# SparkFun_GPS_ZED-F9K.net
KiCad netlist of a schematic drawn in EAGLE
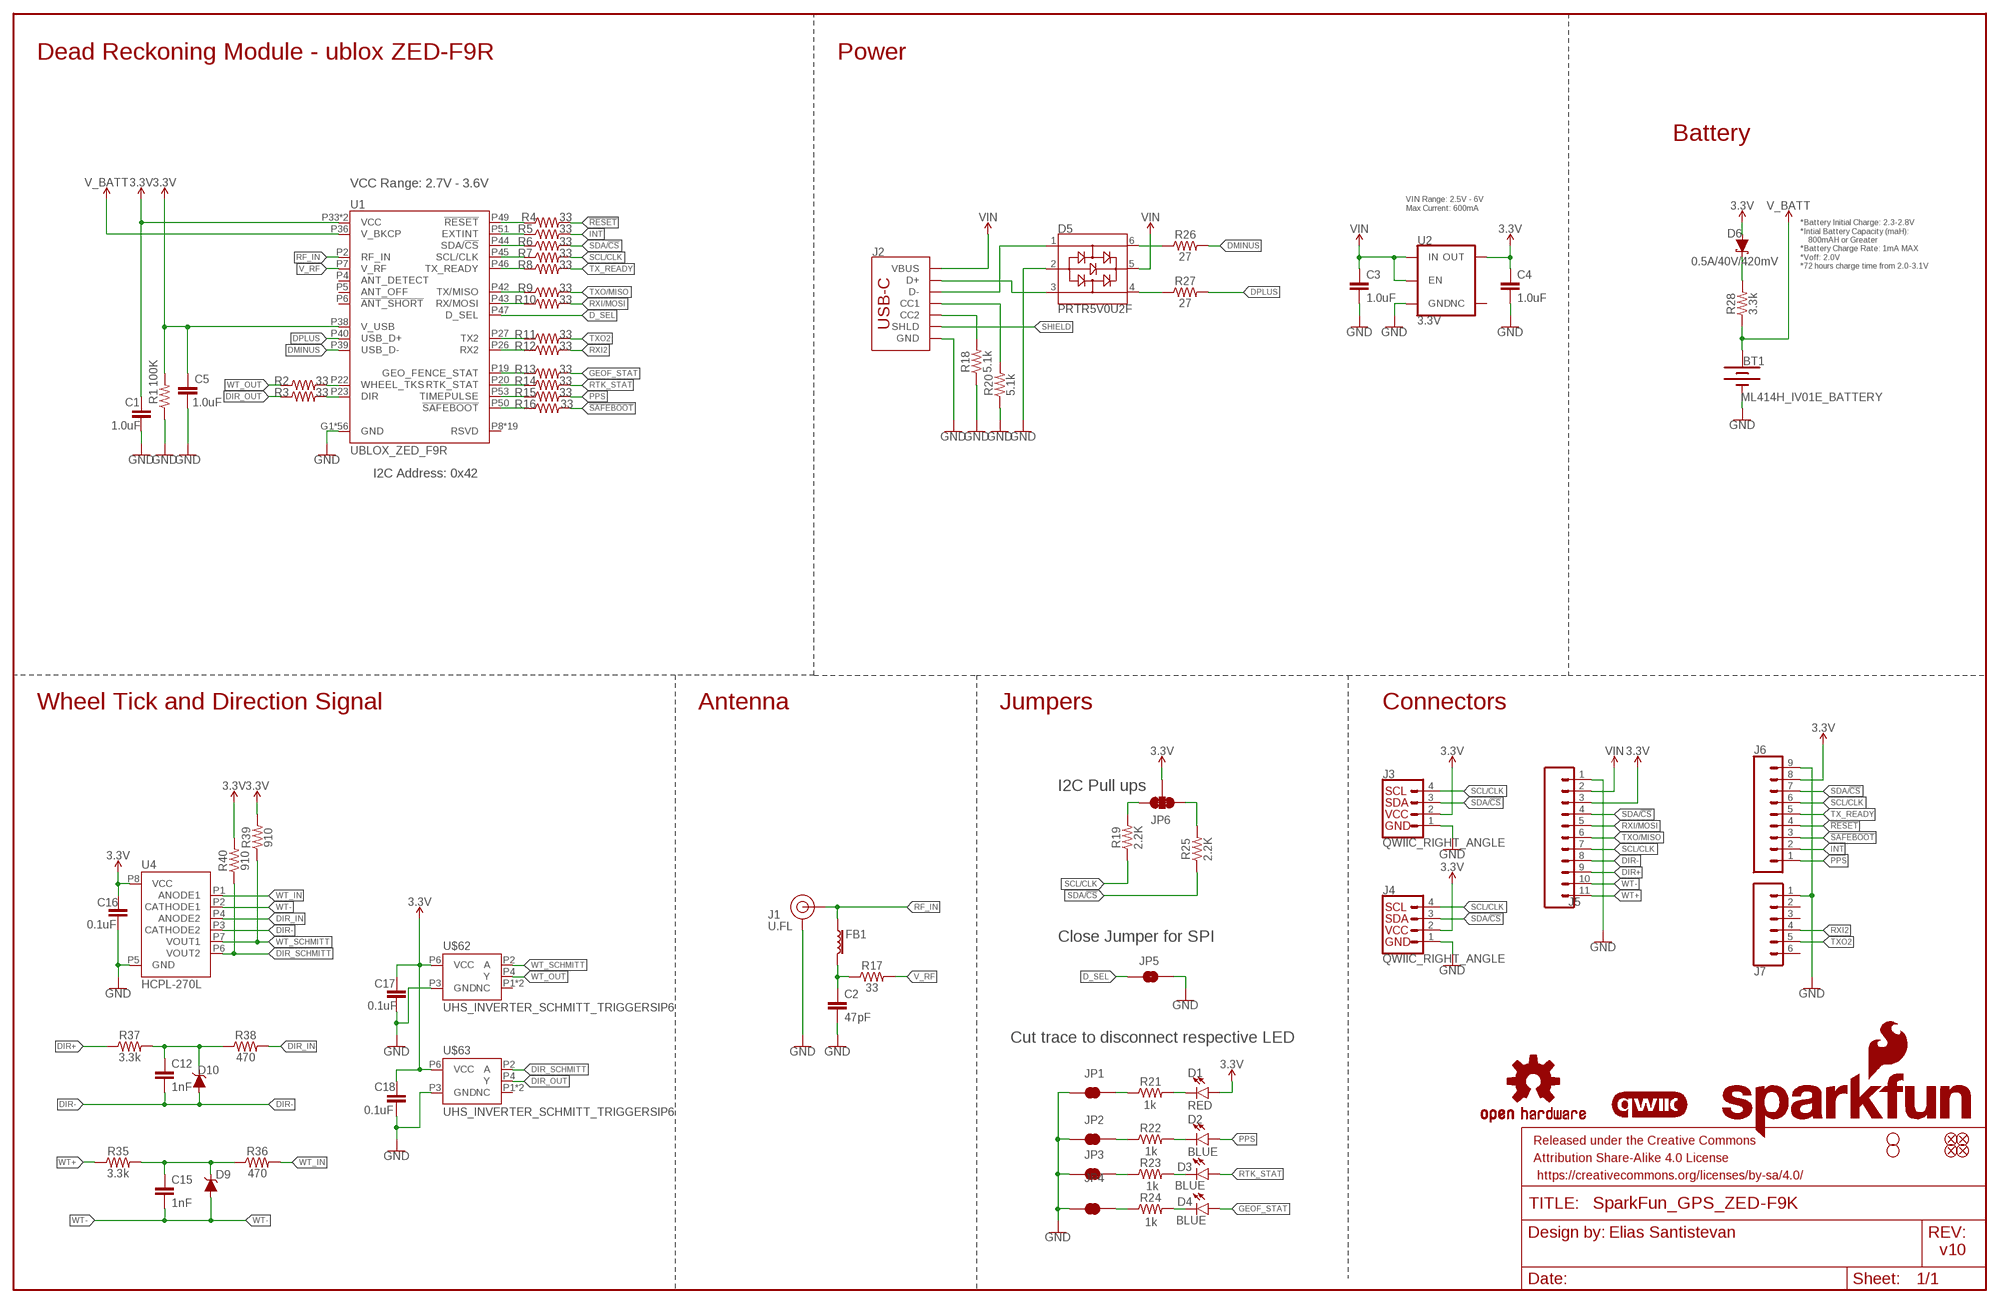
[diagram p0: schematic, sheet 1]

(export (version "E")
  (design (tool "Eeschema 10.0.6"))
  (components
    (comp (ref "$1_36_$_2020-02-13_17-32-45")
      (value "STAND-OFFTIGHT")
      (footprint "eagle-import:STAND-OFF-TIGHT")
      (libsource (lib "eagle-import") (part "STAND-OFFTIGHT"))
    )
    (comp (ref "BT1")
      (value "ML414H_IV01E_BATTERY")
      (footprint "eagle-import:ML414H_IV01E")
      (libsource (lib "eagle-import") (part "ML414H_IV01E_BATTERY"))
    )
    (comp (ref "C1")
      (value "1.0uF")
      (footprint "eagle-import:0603")
      (libsource (lib "eagle-import") (part "1.0UF-0603-16V-10%-X7R"))
    )
    (comp (ref "C2")
      (value "47pF")
      (footprint "eagle-import:0402")
      (libsource (lib "eagle-import") (part "47PF-0402-25V-5%-X7R"))
    )
    (comp (ref "C3")
      (value "1.0uF")
      (footprint "eagle-import:0603")
      (libsource (lib "eagle-import") (part "1.0UF-0603-16V-10%-X7R"))
    )
    (comp (ref "C4")
      (value "1.0uF")
      (footprint "eagle-import:0603")
      (libsource (lib "eagle-import") (part "1.0UF-0603-16V-10%-X7R"))
    )
    (comp (ref "C5")
      (value "1.0uF")
      (footprint "eagle-import:0603")
      (libsource (lib "eagle-import") (part "1.0UF-0603-16V-10%-X7R"))
    )
    (comp (ref "C12")
      (value "1nF")
      (footprint "eagle-import:0402")
      (libsource (lib "eagle-import") (part "1.0NF/1000PF-0402-25V-10%-X7R"))
    )
    (comp (ref "C15")
      (value "1nF")
      (footprint "eagle-import:0402")
      (libsource (lib "eagle-import") (part "1.0NF/1000PF-0402-25V-10%-X7R"))
    )
    (comp (ref "C16")
      (value "0.1uF")
      (footprint "eagle-import:0402")
      (libsource (lib "eagle-import") (part "0.1UF-0402-6.3V-10%-X7R"))
    )
    (comp (ref "C17")
      (value "0.1uF")
      (footprint "eagle-import:0402")
      (libsource (lib "eagle-import") (part "0.1UF-0402-6.3V-10%-X7R"))
    )
    (comp (ref "C18")
      (value "0.1uF")
      (footprint "eagle-import:0402")
      (libsource (lib "eagle-import") (part "0.1UF-0402-6.3V-10%-X7R"))
    )
    (comp (ref "D1")
      (value "RED")
      (footprint "eagle-import:LED-0603")
      (libsource (lib "eagle-import") (part "LED-RED0603"))
    )
    (comp (ref "D2")
      (value "BLUE")
      (footprint "eagle-import:LED-0603")
      (libsource (lib "eagle-import") (part "LED-BLUE0603"))
    )
    (comp (ref "D3")
      (value "BLUE")
      (footprint "eagle-import:LED-0603")
      (libsource (lib "eagle-import") (part "LED-BLUE0603"))
    )
    (comp (ref "D4")
      (value "BLUE")
      (footprint "eagle-import:LED-0603")
      (libsource (lib "eagle-import") (part "LED-BLUE0603"))
    )
    (comp (ref "D5")
      (value "PRTR5V0U2F")
      (footprint "eagle-import:SOT886")
      (libsource (lib "eagle-import") (part "PRTR5V0U2F"))
    )
    (comp (ref "D6")
      (value "0.5A/40V/420mV")
      (footprint "eagle-import:SOD-323")
      (libsource (lib "eagle-import") (part "DIODE-SCHOTTKY-PMEG4005EJ"))
    )
    (comp (ref "D9")
      (value "0.5A/40V/420mV")
      (footprint "eagle-import:SOT23_BZX")
      (libsource (lib "eagle-import") (part "BZX84_DIODE"))
    )
    (comp (ref "D10")
      (value "0.5A/40V/420mV")
      (footprint "eagle-import:SOT23_BZX")
      (libsource (lib "eagle-import") (part "BZX84_DIODE"))
    )
    (comp (ref "FB1")
      (value "120NH")
      (footprint "eagle-import:0402_MURATA")
      (libsource (lib "eagle-import") (part "FERRITE_BEAD_GNSS"))
    )
    (comp (ref "FD1")
      (value "FIDUCIALUFIDUCIAL")
      (footprint "eagle-import:FIDUCIAL-MICRO")
      (libsource (lib "eagle-import") (part "FIDUCIALUFIDUCIAL"))
    )
    (comp (ref "FD2")
      (value "FIDUCIALUFIDUCIAL")
      (footprint "eagle-import:FIDUCIAL-MICRO")
      (libsource (lib "eagle-import") (part "FIDUCIALUFIDUCIAL"))
    )
    (comp (ref "FD3")
      (value "FIDUCIALUFIDUCIAL")
      (footprint "eagle-import:FIDUCIAL-MICRO")
      (libsource (lib "eagle-import") (part "FIDUCIALUFIDUCIAL"))
    )
    (comp (ref "FD4")
      (value "FIDUCIALUFIDUCIAL")
      (footprint "eagle-import:FIDUCIAL-MICRO")
      (libsource (lib "eagle-import") (part "FIDUCIALUFIDUCIAL"))
    )
    (comp (ref "FRAME1")
      (value "FRAME-LEDGER")
      (footprint "eagle-import:CREATIVE_COMMONS")
      (libsource (lib "eagle-import") (part "FRAME-LEDGER"))
    )
    (comp (ref "H2")
      (value "STAND-OFFTIGHT")
      (footprint "eagle-import:STAND-OFF-TIGHT")
      (libsource (lib "eagle-import") (part "STAND-OFFTIGHT"))
    )
    (comp (ref "J1")
      (value "U.FL")
      (footprint "eagle-import:U.FL")
      (libsource (lib "eagle-import") (part "U.FL2PIN"))
    )
    (comp (ref "J2")
      (value "USB_C_2-LAYER_PADS")
      (footprint "eagle-import:USB-C-16P-2LAYER-PADS")
      (libsource (lib "eagle-import") (part "USB_C_2-LAYER_PADS"))
    )
    (comp (ref "J3")
      (value "QWIIC_RIGHT_ANGLE")
      (footprint "eagle-import:JST04_1MM_RA")
      (libsource (lib "eagle-import") (part "QWIIC_CONNECTORJS-1MM"))
    )
    (comp (ref "J4")
      (value "QWIIC_RIGHT_ANGLE")
      (footprint "eagle-import:JST04_1MM_RA")
      (libsource (lib "eagle-import") (part "QWIIC_CONNECTORJS-1MM"))
    )
    (comp (ref "J5")
      (value "CONN_111X11_NO_SILK")
      (footprint "eagle-import:1X11_NO_SILK")
      (libsource (lib "eagle-import") (part "CONN_111X11_NO_SILK"))
    )
    (comp (ref "J6")
      (value "CONN_09NO_SILK")
      (footprint "eagle-import:1X09_NO_SILK")
      (libsource (lib "eagle-import") (part "CONN_09NO_SILK"))
    )
    (comp (ref "J7")
      (value "CONN_06NO_SILK_NO_POP")
      (footprint "eagle-import:1X06_NO_SILK")
      (libsource (lib "eagle-import") (part "CONN_06NO_SILK_NO_POP"))
    )
    (comp (ref "JP1")
      (value "JUMPER-SMT_2_NC_TRACE_SILK")
      (footprint "eagle-import:SMT-JUMPER_2_NC_TRACE_SILK")
      (libsource (lib "eagle-import") (part "JUMPER-SMT_2_NC_TRACE_SILK"))
    )
    (comp (ref "JP2")
      (value "JUMPER-SMT_2_NC_TRACE_SILK")
      (footprint "eagle-import:SMT-JUMPER_2_NC_TRACE_SILK")
      (libsource (lib "eagle-import") (part "JUMPER-SMT_2_NC_TRACE_SILK"))
    )
    (comp (ref "JP3")
      (value "JUMPER-SMT_2_NC_TRACE_SILK")
      (footprint "eagle-import:SMT-JUMPER_2_NC_TRACE_SILK")
      (libsource (lib "eagle-import") (part "JUMPER-SMT_2_NC_TRACE_SILK"))
    )
    (comp (ref "JP4")
      (value "JUMPER-SMT_2_NC_TRACE_SILK")
      (footprint "eagle-import:SMT-JUMPER_2_NC_TRACE_SILK")
      (libsource (lib "eagle-import") (part "JUMPER-SMT_2_NC_TRACE_SILK"))
    )
    (comp (ref "JP5")
      (value "JUMPER-SMT_2_NO_SILK")
      (footprint "eagle-import:SMT-JUMPER_2_NO_SILK")
      (libsource (lib "eagle-import") (part "JUMPER-SMT_2_NO_SILK"))
    )
    (comp (ref "JP6")
      (value "JUMPER-SMT_3_2-NC_TRACE_SILK")
      (footprint "eagle-import:SMT-JUMPER_3_2-NC_TRACE_SILK")
      (libsource (lib "eagle-import") (part "JUMPER-SMT_3_2-NC_TRACE_SILK"))
    )
    (comp (ref "LOGO1")
      (value "OSHW-LOGOM")
      (footprint "eagle-import:OSHW-LOGO-M")
      (libsource (lib "eagle-import") (part "OSHW-LOGOM"))
    )
    (comp (ref "LOGO2")
      (value "QWIIC_LOGO_4MM")
      (footprint "eagle-import:QWIIC_4MM")
      (libsource (lib "eagle-import") (part "QWIIC_LOGO_4MM"))
    )
    (comp (ref "LOGO3")
      (value "SFE_LOGO_NAME_FLAME.2_INCH")
      (footprint "eagle-import:SFE_LOGO_NAME_FLAME_.2")
      (libsource (lib "eagle-import") (part "SFE_LOGO_NAME_FLAME.2_INCH"))
    )
    (comp (ref "R1")
      (value "100K")
      (footprint "eagle-import:0402")
      (libsource (lib "eagle-import") (part "100KOHM-0402-1/16W-1%"))
    )
    (comp (ref "R2")
      (value "33")
      (footprint "eagle-import:0402")
      (libsource (lib "eagle-import") (part "33OHM-0402-1/10W-1%"))
    )
    (comp (ref "R3")
      (value "33")
      (footprint "eagle-import:0402")
      (libsource (lib "eagle-import") (part "33OHM-0402-1/10W-1%"))
    )
    (comp (ref "R4")
      (value "33")
      (footprint "eagle-import:0402")
      (libsource (lib "eagle-import") (part "33OHM-0402-1/10W-1%"))
    )
    (comp (ref "R5")
      (value "33")
      (footprint "eagle-import:0402")
      (libsource (lib "eagle-import") (part "33OHM-0402-1/10W-1%"))
    )
    (comp (ref "R6")
      (value "33")
      (footprint "eagle-import:0402")
      (libsource (lib "eagle-import") (part "33OHM-0402-1/10W-1%"))
    )
    (comp (ref "R7")
      (value "33")
      (footprint "eagle-import:0402")
      (libsource (lib "eagle-import") (part "33OHM-0402-1/10W-1%"))
    )
    (comp (ref "R8")
      (value "33")
      (footprint "eagle-import:0402")
      (libsource (lib "eagle-import") (part "33OHM-0402-1/10W-1%"))
    )
    (comp (ref "R9")
      (value "33")
      (footprint "eagle-import:0402")
      (libsource (lib "eagle-import") (part "33OHM-0402-1/10W-1%"))
    )
    (comp (ref "R10")
      (value "33")
      (footprint "eagle-import:0402")
      (libsource (lib "eagle-import") (part "33OHM-0402-1/10W-1%"))
    )
    (comp (ref "R11")
      (value "33")
      (footprint "eagle-import:0402")
      (libsource (lib "eagle-import") (part "33OHM-0402-1/10W-1%"))
    )
    (comp (ref "R12")
      (value "33")
      (footprint "eagle-import:0402")
      (libsource (lib "eagle-import") (part "33OHM-0402-1/10W-1%"))
    )
    (comp (ref "R13")
      (value "33")
      (footprint "eagle-import:0402")
      (libsource (lib "eagle-import") (part "33OHM-0402-1/10W-1%"))
    )
    (comp (ref "R14")
      (value "33")
      (footprint "eagle-import:0402")
      (libsource (lib "eagle-import") (part "33OHM-0402-1/10W-1%"))
    )
    (comp (ref "R15")
      (value "33")
      (footprint "eagle-import:0402")
      (libsource (lib "eagle-import") (part "33OHM-0402-1/10W-1%"))
    )
    (comp (ref "R16")
      (value "33")
      (footprint "eagle-import:0402")
      (libsource (lib "eagle-import") (part "33OHM-0402-1/10W-1%"))
    )
    (comp (ref "R17")
      (value "33")
      (footprint "eagle-import:0603")
      (libsource (lib "eagle-import") (part "33OHM-0603-1/10W-1%"))
    )
    (comp (ref "R18")
      (value "5.1k")
      (footprint "eagle-import:0402")
      (libsource (lib "eagle-import") (part "5.1KOHM-0402-1/16W-1%"))
    )
    (comp (ref "R19")
      (value "2.2K")
      (footprint "eagle-import:0402")
      (libsource (lib "eagle-import") (part "2.2KOHM-0402-1/16W-1%"))
    )
    (comp (ref "R20")
      (value "5.1k")
      (footprint "eagle-import:0402")
      (libsource (lib "eagle-import") (part "5.1KOHM-0402-1/16W-1%"))
    )
    (comp (ref "R21")
      (value "1KOHM-0402-1/16W-1%")
      (footprint "eagle-import:0402")
      (libsource (lib "eagle-import") (part "1KOHM-0402-1/16W-1%"))
    )
    (comp (ref "R22")
      (value "1KOHM-0402-1/16W-1%")
      (footprint "eagle-import:0402")
      (libsource (lib "eagle-import") (part "1KOHM-0402-1/16W-1%"))
    )
    (comp (ref "R23")
      (value "1KOHM-0402-1/16W-1%")
      (footprint "eagle-import:0402")
      (libsource (lib "eagle-import") (part "1KOHM-0402-1/16W-1%"))
    )
    (comp (ref "R24")
      (value "1KOHM-0402-1/16W-1%")
      (footprint "eagle-import:0402")
      (libsource (lib "eagle-import") (part "1KOHM-0402-1/16W-1%"))
    )
    (comp (ref "R25")
      (value "2.2K")
      (footprint "eagle-import:0402")
      (libsource (lib "eagle-import") (part "2.2KOHM-0402-1/16W-1%"))
    )
    (comp (ref "R26")
      (value "27")
      (footprint "eagle-import:0603")
      (libsource (lib "eagle-import") (part "27OHM-0603-1/10W-1%"))
    )
    (comp (ref "R27")
      (value "27")
      (footprint "eagle-import:0603")
      (libsource (lib "eagle-import") (part "27OHM-0603-1/10W-1%"))
    )
    (comp (ref "R28")
      (value "3.3k")
      (footprint "eagle-import:0603")
      (libsource (lib "eagle-import") (part "3.3KOHM-0603-1/10W-1%"))
    )
    (comp (ref "R35")
      (value "3.3k")
      (footprint "eagle-import:0603")
      (libsource (lib "eagle-import") (part "3.3KOHM-0603-1/10W-1%"))
    )
    (comp (ref "R36")
      (value "470")
      (footprint "eagle-import:0603")
      (libsource (lib "eagle-import") (part "470OHM-0603-1/10W-1%"))
    )
    (comp (ref "R37")
      (value "3.3k")
      (footprint "eagle-import:0603")
      (libsource (lib "eagle-import") (part "3.3KOHM-0603-1/10W-1%"))
    )
    (comp (ref "R38")
      (value "470")
      (footprint "eagle-import:0603")
      (libsource (lib "eagle-import") (part "470OHM-0603-1/10W-1%"))
    )
    (comp (ref "R39")
      (value "910")
      (footprint "eagle-import:0603")
      (libsource (lib "eagle-import") (part "910OHM-0603-1/10W-5%"))
    )
    (comp (ref "R40")
      (value "910")
      (footprint "eagle-import:0603")
      (libsource (lib "eagle-import") (part "910OHM-0603-1/10W-5%"))
    )
    (comp (ref "U$62")
      (value "UHS_INVERTER_SCHMITT_TRIGGERSIP6")
      (footprint "eagle-import:SIP6")
      (libsource (lib "eagle-import") (part "UHS_INVERTER_SCHMITT_TRIGGERSIP6"))
    )
    (comp (ref "U$63")
      (value "UHS_INVERTER_SCHMITT_TRIGGERSIP6")
      (footprint "eagle-import:SIP6")
      (libsource (lib "eagle-import") (part "UHS_INVERTER_SCHMITT_TRIGGERSIP6"))
    )
    (comp (ref "U1")
      (value "UBLOX_ZED_F9R")
      (footprint "eagle-import:UBLOX_ZED_F9R")
      (libsource (lib "eagle-import") (part "UBLOX_ZED_F9R"))
    )
    (comp (ref "U2")
      (value "3.3V")
      (footprint "eagle-import:SOT23-5")
      (libsource (lib "eagle-import") (part "V_REG_AP2112K-3.3V"))
    )
    (comp (ref "U4")
      (value "HCPL-270L")
      (footprint "eagle-import:SOP_8-PIN")
      (libsource (lib "eagle-import") (part "HCPL-270L"))
    )
  )
  (nets
    (net (code "1") (name "/SDA{slash}~{CS}") (class "Default")
      (node (ref "J3") (pin "3") (pinfunction "3_3") (pintype "passive"))
      (node (ref "J4") (pin "3") (pinfunction "3_3") (pintype "passive"))
      (node (ref "J5") (pin "4") (pinfunction "4_4") (pintype "passive"))
      (node (ref "J6") (pin "7") (pinfunction "7_7") (pintype "passive"))
      (node (ref "R25") (pin "1") (pinfunction "1_1") (pintype "passive"))
      (node (ref "R6") (pin "2") (pinfunction "2_2") (pintype "passive"))
    )
    (net (code "2") (name "/~{RESET}") (class "Default")
      (node (ref "J6") (pin "4") (pinfunction "4_4") (pintype "passive"))
      (node (ref "R4") (pin "2") (pinfunction "2_2") (pintype "passive"))
    )
    (net (code "3") (name "/~{SAFEBOOT}") (class "Default")
      (node (ref "J6") (pin "3") (pinfunction "3_3") (pintype "passive"))
      (node (ref "R16") (pin "2") (pinfunction "2_2") (pintype "passive"))
    )
    (net (code "4") (name "3.3V") (class "Default")
      (node (ref "C1") (pin "1") (pinfunction "1_1") (pintype "passive"))
      (node (ref "C16") (pin "1") (pinfunction "1_1") (pintype "passive"))
      (node (ref "C17") (pin "1") (pinfunction "1_1") (pintype "passive"))
      (node (ref "C18") (pin "1") (pinfunction "1_1") (pintype "passive"))
      (node (ref "C4") (pin "1") (pinfunction "1_1") (pintype "passive"))
      (node (ref "C5") (pin "1") (pinfunction "1_1") (pintype "passive"))
      (node (ref "D1") (pin "A") (pinfunction "A_A") (pintype "passive"))
      (node (ref "D6") (pin "A") (pinfunction "A_A") (pintype "passive"))
      (node (ref "J3") (pin "2") (pinfunction "2_2") (pintype "power_in"))
      (node (ref "J4") (pin "2") (pinfunction "2_2") (pintype "power_in"))
      (node (ref "J5") (pin "3") (pinfunction "3_3") (pintype "passive"))
      (node (ref "J6") (pin "8") (pinfunction "8_8") (pintype "passive"))
      (node (ref "JP6") (pin "2") (pinfunction "2_2") (pintype "passive"))
      (node (ref "R1") (pin "2") (pinfunction "2_2") (pintype "passive"))
      (node (ref "R39") (pin "2") (pinfunction "2_2") (pintype "passive"))
      (node (ref "R40") (pin "2") (pinfunction "2_2") (pintype "passive"))
      (node (ref "U$62") (pin "P6") (pinfunction "VCC_P6") (pintype "power_in"))
      (node (ref "U$63") (pin "P6") (pinfunction "VCC_P6") (pintype "power_in"))
      (node (ref "U1") (pin "P33") (pinfunction "VCC_P33") (pintype "power_in"))
      (node (ref "U1") (pin "P34") (pinfunction "VCC_P34") (pintype "power_in"))
      (node (ref "U1") (pin "P38") (pinfunction "V_USB_P38") (pintype "power_in"))
      (node (ref "U2") (pin "5") (pinfunction "OUT_5") (pintype "passive"))
      (node (ref "U4") (pin "P8") (pinfunction "VCC_P8") (pintype "power_in"))
    )
    (net (code "5") (name "DIR+") (class "Default")
      (node (ref "J5") (pin "9") (pinfunction "9_9") (pintype "passive"))
      (node (ref "R37") (pin "1") (pinfunction "1_1") (pintype "passive"))
    )
    (net (code "6") (name "DIR-") (class "Default")
      (node (ref "C12") (pin "2") (pinfunction "2_2") (pintype "passive"))
      (node (ref "D10") (pin "P1") (pinfunction "A_P1") (pintype "passive"))
      (node (ref "J5") (pin "8") (pinfunction "8_8") (pintype "passive"))
      (node (ref "U4") (pin "P3") (pinfunction "CATHODE2_P3") (pintype "input"))
    )
    (net (code "7") (name "DIR_IN") (class "Default")
      (node (ref "R38") (pin "2") (pinfunction "2_2") (pintype "passive"))
      (node (ref "U4") (pin "P4") (pinfunction "ANODE2_P4") (pintype "input"))
    )
    (net (code "8") (name "DIR_OUT") (class "Default")
      (node (ref "R3") (pin "1") (pinfunction "1_1") (pintype "passive"))
      (node (ref "U$63") (pin "P4") (pinfunction "Y_P4") (pintype "bidirectional"))
    )
    (net (code "9") (name "DIR_SCHMITT") (class "Default")
      (node (ref "R40") (pin "1") (pinfunction "1_1") (pintype "passive"))
      (node (ref "U$63") (pin "P2") (pinfunction "A_P2") (pintype "bidirectional"))
      (node (ref "U4") (pin "P6") (pinfunction "VOUT2_P6") (pintype "output"))
    )
    (net (code "10") (name "DMINUS") (class "Default")
      (node (ref "R26") (pin "2") (pinfunction "2_2") (pintype "passive"))
      (node (ref "U1") (pin "P39") (pinfunction "USB_D-_P39") (pintype "bidirectional"))
    )
    (net (code "11") (name "DPLUS") (class "Default")
      (node (ref "R27") (pin "2") (pinfunction "2_2") (pintype "passive"))
      (node (ref "U1") (pin "P40") (pinfunction "USB_D+_P40") (pintype "bidirectional"))
    )
    (net (code "12") (name "D_SEL") (class "Default")
      (node (ref "JP5") (pin "1") (pinfunction "1_1") (pintype "passive"))
      (node (ref "U1") (pin "P47") (pinfunction "D_SEL_P47") (pintype "bidirectional"))
    )
    (net (code "13") (name "GEOF_STAT") (class "Default")
      (node (ref "D4") (pin "A") (pinfunction "A_A") (pintype "passive"))
      (node (ref "R13") (pin "2") (pinfunction "2_2") (pintype "passive"))
    )
    (net (code "14") (name "GND") (class "Default")
      (node (ref "BT1") (pin "-") (pinfunction "-_-") (pintype "power_in"))
      (node (ref "C1") (pin "2") (pinfunction "2_2") (pintype "passive"))
      (node (ref "C16") (pin "2") (pinfunction "2_2") (pintype "passive"))
      (node (ref "C17") (pin "2") (pinfunction "2_2") (pintype "passive"))
      (node (ref "C18") (pin "2") (pinfunction "2_2") (pintype "passive"))
      (node (ref "C2") (pin "2") (pinfunction "2_2") (pintype "passive"))
      (node (ref "C3") (pin "2") (pinfunction "2_2") (pintype "passive"))
      (node (ref "C4") (pin "2") (pinfunction "2_2") (pintype "passive"))
      (node (ref "C5") (pin "2") (pinfunction "2_2") (pintype "passive"))
      (node (ref "D5") (pin "2") (pinfunction "2_2") (pintype "bidirectional"))
      (node (ref "J1") (pin "1") (pinfunction "GND_1") (pintype "bidirectional"))
      (node (ref "J1") (pin "2") (pinfunction "GND_2") (pintype "bidirectional"))
      (node (ref "J2") (pin "GND") (pinfunction "GND_GND") (pintype "bidirectional"))
      (node (ref "J2") (pin "GND2") (pinfunction "GND_GND2") (pintype "bidirectional"))
      (node (ref "J3") (pin "1") (pinfunction "1_1") (pintype "power_in"))
      (node (ref "J4") (pin "1") (pinfunction "1_1") (pintype "power_in"))
      (node (ref "J5") (pin "1") (pinfunction "1_1") (pintype "passive"))
      (node (ref "J6") (pin "9") (pinfunction "9_9") (pintype "passive"))
      (node (ref "J7") (pin "1") (pinfunction "1_1") (pintype "passive"))
      (node (ref "JP1") (pin "1") (pinfunction "1_1") (pintype "passive"))
      (node (ref "JP2") (pin "1") (pinfunction "1_1") (pintype "passive"))
      (node (ref "JP3") (pin "1") (pinfunction "1_1") (pintype "passive"))
      (node (ref "JP4") (pin "1") (pinfunction "1_1") (pintype "passive"))
      (node (ref "JP5") (pin "2") (pinfunction "2_2") (pintype "passive"))
      (node (ref "R1") (pin "1") (pinfunction "1_1") (pintype "passive"))
      (node (ref "R18") (pin "1") (pinfunction "1_1") (pintype "passive"))
      (node (ref "R20") (pin "1") (pinfunction "1_1") (pintype "passive"))
      (node (ref "U$62") (pin "P3") (pinfunction "GND_P3") (pintype "power_in"))
      (node (ref "U$63") (pin "P3") (pinfunction "GND_P3") (pintype "power_in"))
      (node (ref "U1") (pin "G1") (pinfunction "GND_G1") (pintype "power_in"))
      (node (ref "U1") (pin "G10") (pinfunction "GND_G10") (pintype "power_in"))
      (node (ref "U1") (pin "G11") (pinfunction "GND_G11") (pintype "power_in"))
      (node (ref "U1") (pin "G12") (pinfunction "GND_G12") (pintype "power_in"))
      (node (ref "U1") (pin "G13") (pinfunction "GND_G13") (pintype "power_in"))
      (node (ref "U1") (pin "G14") (pinfunction "GND_G14") (pintype "power_in"))
      (node (ref "U1") (pin "G15") (pinfunction "GND_G15") (pintype "power_in"))
      (node (ref "U1") (pin "G16") (pinfunction "GND_G16") (pintype "power_in"))
      (node (ref "U1") (pin "G17") (pinfunction "GND_G17") (pintype "power_in"))
      (node (ref "U1") (pin "G18") (pinfunction "GND_G18") (pintype "power_in"))
      (node (ref "U1") (pin "G19") (pinfunction "GND_G19") (pintype "power_in"))
      (node (ref "U1") (pin "G2") (pinfunction "GND_G2") (pintype "power_in"))
      (node (ref "U1") (pin "G20") (pinfunction "GND_G20") (pintype "power_in"))
      (node (ref "U1") (pin "G21") (pinfunction "GND_G21") (pintype "power_in"))
      (node (ref "U1") (pin "G22") (pinfunction "GND_G22") (pintype "power_in"))
      (node (ref "U1") (pin "G23") (pinfunction "GND_G23") (pintype "power_in"))
      (node (ref "U1") (pin "G24") (pinfunction "GND_G24") (pintype "power_in"))
      (node (ref "U1") (pin "G25") (pinfunction "GND_G25") (pintype "power_in"))
      (node (ref "U1") (pin "G26") (pinfunction "GND_G26") (pintype "power_in"))
      (node (ref "U1") (pin "G27") (pinfunction "GND_G27") (pintype "power_in"))
      (node (ref "U1") (pin "G28") (pinfunction "GND_G28") (pintype "power_in"))
      (node (ref "U1") (pin "G29") (pinfunction "GND_G29") (pintype "power_in"))
      (node (ref "U1") (pin "G3") (pinfunction "GND_G3") (pintype "power_in"))
      (node (ref "U1") (pin "G30") (pinfunction "GND_G30") (pintype "power_in"))
      (node (ref "U1") (pin "G31") (pinfunction "GND_G31") (pintype "power_in"))
      (node (ref "U1") (pin "G32") (pinfunction "GND_G32") (pintype "power_in"))
      (node (ref "U1") (pin "G33") (pinfunction "GND_G33") (pintype "power_in"))
      (node (ref "U1") (pin "G34") (pinfunction "GND_G34") (pintype "power_in"))
      (node (ref "U1") (pin "G35") (pinfunction "GND_G35") (pintype "power_in"))
      (node (ref "U1") (pin "G36") (pinfunction "GND_G36") (pintype "power_in"))
      (node (ref "U1") (pin "G37") (pinfunction "GND_G37") (pintype "power_in"))
      (node (ref "U1") (pin "G38") (pinfunction "GND_G38") (pintype "power_in"))
      (node (ref "U1") (pin "G39") (pinfunction "GND_G39") (pintype "power_in"))
      (node (ref "U1") (pin "G4") (pinfunction "GND_G4") (pintype "power_in"))
      (node (ref "U1") (pin "G40") (pinfunction "GND_G40") (pintype "power_in"))
      (node (ref "U1") (pin "G41") (pinfunction "GND_G41") (pintype "power_in"))
      (node (ref "U1") (pin "G42") (pinfunction "GND_G42") (pintype "power_in"))
      (node (ref "U1") (pin "G43") (pinfunction "GND_G43") (pintype "power_in"))
      (node (ref "U1") (pin "G44") (pinfunction "GND_G44") (pintype "power_in"))
      (node (ref "U1") (pin "G45") (pinfunction "GND_G45") (pintype "power_in"))
      (node (ref "U1") (pin "G46") (pinfunction "GND_G46") (pintype "power_in"))
      (node (ref "U1") (pin "G47") (pinfunction "GND_G47") (pintype "power_in"))
      (node (ref "U1") (pin "G48") (pinfunction "GND_G48") (pintype "power_in"))
      (node (ref "U1") (pin "G5") (pinfunction "GND_G5") (pintype "power_in"))
      (node (ref "U1") (pin "G6") (pinfunction "GND_G6") (pintype "power_in"))
      (node (ref "U1") (pin "G7") (pinfunction "GND_G7") (pintype "power_in"))
      (node (ref "U1") (pin "G8") (pinfunction "GND_G8") (pintype "power_in"))
      (node (ref "U1") (pin "G9") (pinfunction "GND_G9") (pintype "power_in"))
      (node (ref "U1") (pin "P1") (pinfunction "GND_P1") (pintype "power_in"))
      (node (ref "U1") (pin "P12") (pinfunction "GND_P12") (pintype "power_in"))
      (node (ref "U1") (pin "P14") (pinfunction "GND_P14") (pintype "power_in"))
      (node (ref "U1") (pin "P3") (pinfunction "GND_P3") (pintype "power_in"))
      (node (ref "U1") (pin "P32") (pinfunction "GND_P32") (pintype "power_in"))
      (node (ref "U1") (pin "P37") (pinfunction "GND_P37") (pintype "power_in"))
      (node (ref "U1") (pin "P41") (pinfunction "GND_P41") (pintype "power_in"))
      (node (ref "U1") (pin "P48") (pinfunction "GND_P48") (pintype "power_in"))
      (node (ref "U2") (pin "2") (pinfunction "GND_2") (pintype "input"))
      (node (ref "U4") (pin "P5") (pinfunction "GND_P5") (pintype "power_in"))
    )
    (net (code "15") (name "INT") (class "Default")
      (node (ref "J6") (pin "2") (pinfunction "2_2") (pintype "passive"))
      (node (ref "R5") (pin "2") (pinfunction "2_2") (pintype "passive"))
    )
    (net (code "16") (name "Net-(D1-PadC)") (class "Default")
      (node (ref "D1") (pin "C") (pinfunction "C_C") (pintype "passive"))
      (node (ref "R21") (pin "2") (pinfunction "2_2") (pintype "passive"))
    )
    (net (code "17") (name "Net-(D2-PadC)") (class "Default")
      (node (ref "D2") (pin "C") (pinfunction "C_C") (pintype "passive"))
      (node (ref "R22") (pin "2") (pinfunction "2_2") (pintype "passive"))
    )
    (net (code "18") (name "Net-(D3-PadC)") (class "Default")
      (node (ref "D3") (pin "C") (pinfunction "C_C") (pintype "passive"))
      (node (ref "R23") (pin "2") (pinfunction "2_2") (pintype "passive"))
    )
    (net (code "19") (name "Net-(D4-PadC)") (class "Default")
      (node (ref "D4") (pin "C") (pinfunction "C_C") (pintype "passive"))
      (node (ref "R24") (pin "2") (pinfunction "2_2") (pintype "passive"))
    )
    (net (code "20") (name "Net-(D5-Pad1)") (class "Default")
      (node (ref "D5") (pin "1") (pinfunction "1_1") (pintype "bidirectional"))
      (node (ref "J2") (pin "A7") (pinfunction "D-_A7") (pintype "bidirectional"))
      (node (ref "J2") (pin "B7") (pinfunction "D-_B7") (pintype "bidirectional"))
    )
    (net (code "21") (name "Net-(D5-Pad3)") (class "Default")
      (node (ref "D5") (pin "3") (pinfunction "3_3") (pintype "bidirectional"))
      (node (ref "J2") (pin "A6") (pinfunction "D+_A6") (pintype "bidirectional"))
      (node (ref "J2") (pin "B6") (pinfunction "D+_B6") (pintype "bidirectional"))
    )
    (net (code "22") (name "Net-(D5-Pad4)") (class "Default")
      (node (ref "D5") (pin "4") (pinfunction "4_4") (pintype "bidirectional"))
      (node (ref "R27") (pin "1") (pinfunction "1_1") (pintype "passive"))
    )
    (net (code "23") (name "Net-(D5-Pad6)") (class "Default")
      (node (ref "D5") (pin "6") (pinfunction "6_6") (pintype "bidirectional"))
      (node (ref "R26") (pin "1") (pinfunction "1_1") (pintype "passive"))
    )
    (net (code "24") (name "Net-(D6-PadC)") (class "Default")
      (node (ref "D6") (pin "C") (pinfunction "C_C") (pintype "passive"))
      (node (ref "R28") (pin "2") (pinfunction "2_2") (pintype "passive"))
    )
    (net (code "25") (name "Net-(D9-C)") (class "Default")
      (node (ref "C15") (pin "1") (pinfunction "1_1") (pintype "passive"))
      (node (ref "D9") (pin "P3") (pinfunction "C_P3") (pintype "passive"))
      (node (ref "R35") (pin "2") (pinfunction "2_2") (pintype "passive"))
      (node (ref "R36") (pin "1") (pinfunction "1_1") (pintype "passive"))
    )
    (net (code "26") (name "Net-(D10-C)") (class "Default")
      (node (ref "C12") (pin "1") (pinfunction "1_1") (pintype "passive"))
      (node (ref "D10") (pin "P3") (pinfunction "C_P3") (pintype "passive"))
      (node (ref "R37") (pin "2") (pinfunction "2_2") (pintype "passive"))
      (node (ref "R38") (pin "1") (pinfunction "1_1") (pintype "passive"))
    )
    (net (code "27") (name "Net-(FB1-2)") (class "Default")
      (node (ref "C2") (pin "1") (pinfunction "1_1") (pintype "passive"))
      (node (ref "FB1") (pin "P2") (pinfunction "2_P2") (pintype "passive"))
      (node (ref "R17") (pin "1") (pinfunction "1_1") (pintype "passive"))
    )
    (net (code "28") (name "Net-(J2-CC1)") (class "Default")
      (node (ref "J2") (pin "A5") (pinfunction "CC1_A5") (pintype "bidirectional"))
      (node (ref "R20") (pin "2") (pinfunction "2_2") (pintype "passive"))
    )
    (net (code "29") (name "Net-(J2-CC2)") (class "Default")
      (node (ref "J2") (pin "B5") (pinfunction "CC2_B5") (pintype "bidirectional"))
      (node (ref "R18") (pin "2") (pinfunction "2_2") (pintype "passive"))
    )
    (net (code "30") (name "Net-(JP1-Pad2)") (class "Default")
      (node (ref "JP1") (pin "2") (pinfunction "2_2") (pintype "passive"))
      (node (ref "R21") (pin "1") (pinfunction "1_1") (pintype "passive"))
    )
    (net (code "31") (name "Net-(JP2-Pad2)") (class "Default")
      (node (ref "JP2") (pin "2") (pinfunction "2_2") (pintype "passive"))
      (node (ref "R22") (pin "1") (pinfunction "1_1") (pintype "passive"))
    )
    (net (code "32") (name "Net-(JP3-Pad2)") (class "Default")
      (node (ref "JP3") (pin "2") (pinfunction "2_2") (pintype "passive"))
      (node (ref "R23") (pin "1") (pinfunction "1_1") (pintype "passive"))
    )
    (net (code "33") (name "Net-(JP4-Pad2)") (class "Default")
      (node (ref "JP4") (pin "2") (pinfunction "2_2") (pintype "passive"))
      (node (ref "R24") (pin "1") (pinfunction "1_1") (pintype "passive"))
    )
    (net (code "34") (name "Net-(JP6-Pad1)") (class "Default")
      (node (ref "JP6") (pin "1") (pinfunction "1_1") (pintype "passive"))
      (node (ref "R25") (pin "2") (pinfunction "2_2") (pintype "passive"))
    )
    (net (code "35") (name "Net-(JP6-Pad3)") (class "Default")
      (node (ref "JP6") (pin "3") (pinfunction "3_3") (pintype "passive"))
      (node (ref "R19") (pin "2") (pinfunction "2_2") (pintype "passive"))
    )
    (net (code "36") (name "Net-(U1-DIR)") (class "Default")
      (node (ref "R3") (pin "2") (pinfunction "2_2") (pintype "passive"))
      (node (ref "U1") (pin "P23") (pinfunction "DIR_P23") (pintype "input"))
    )
    (net (code "37") (name "Net-(U1-EXTINT)") (class "Default")
      (node (ref "R5") (pin "1") (pinfunction "1_1") (pintype "passive"))
      (node (ref "U1") (pin "P51") (pinfunction "EXTINT_P51") (pintype "bidirectional"))
    )
    (net (code "38") (name "Net-(U1-GEO_FENCE_STAT)") (class "Default")
      (node (ref "R13") (pin "1") (pinfunction "1_1") (pintype "passive"))
      (node (ref "U1") (pin "P19") (pinfunction "GEO_FENCE_STAT_P19") (pintype "output"))
    )
    (net (code "39") (name "Net-(U1-RTK_STAT)") (class "Default")
      (node (ref "R14") (pin "1") (pinfunction "1_1") (pintype "passive"))
      (node (ref "U1") (pin "P20") (pinfunction "RTK_STAT_P20") (pintype "output"))
    )
    (net (code "40") (name "Net-(U1-RX2)") (class "Default")
      (node (ref "R12") (pin "1") (pinfunction "1_1") (pintype "passive"))
      (node (ref "U1") (pin "P26") (pinfunction "RX2_P26") (pintype "input"))
    )
    (net (code "41") (name "Net-(U1-RX{slash}MOSI)") (class "Default")
      (node (ref "R10") (pin "1") (pinfunction "1_1") (pintype "passive"))
      (node (ref "U1") (pin "P43") (pinfunction "RX/MOSI_P43") (pintype "bidirectional"))
    )
    (net (code "42") (name "Net-(U1-SCL{slash}CLK)") (class "Default")
      (node (ref "R7") (pin "1") (pinfunction "1_1") (pintype "passive"))
      (node (ref "U1") (pin "P45") (pinfunction "SCL/CLK_P45") (pintype "bidirectional"))
    )
    (net (code "43") (name "Net-(U1-SDA{slash}~{CS})") (class "Default")
      (node (ref "R6") (pin "1") (pinfunction "1_1") (pintype "passive"))
      (node (ref "U1") (pin "P44") (pinfunction "SDA/~{CS}_P44") (pintype "bidirectional"))
    )
    (net (code "44") (name "Net-(U1-TIMEPULSE)") (class "Default")
      (node (ref "R15") (pin "1") (pinfunction "1_1") (pintype "passive"))
      (node (ref "U1") (pin "P53") (pinfunction "TIMEPULSE_P53") (pintype "output"))
    )
    (net (code "45") (name "Net-(U1-TX2)") (class "Default")
      (node (ref "R11") (pin "1") (pinfunction "1_1") (pintype "passive"))
      (node (ref "U1") (pin "P27") (pinfunction "TX2_P27") (pintype "output"))
    )
    (net (code "46") (name "Net-(U1-TX_READY)") (class "Default")
      (node (ref "R8") (pin "1") (pinfunction "1_1") (pintype "passive"))
      (node (ref "U1") (pin "P46") (pinfunction "TX_READY_P46") (pintype "bidirectional"))
    )
    (net (code "47") (name "Net-(U1-TX{slash}MISO)") (class "Default")
      (node (ref "R9") (pin "1") (pinfunction "1_1") (pintype "passive"))
      (node (ref "U1") (pin "P42") (pinfunction "TX/MISO_P42") (pintype "bidirectional"))
    )
    (net (code "48") (name "Net-(U1-WHEEL_TKS)") (class "Default")
      (node (ref "R2") (pin "2") (pinfunction "2_2") (pintype "passive"))
      (node (ref "U1") (pin "P22") (pinfunction "WHEEL_TKS_P22") (pintype "input"))
    )
    (net (code "49") (name "Net-(U1-~{RESET})") (class "Default")
      (node (ref "R4") (pin "1") (pinfunction "1_1") (pintype "passive"))
      (node (ref "U1") (pin "P49") (pinfunction "~{RESET}_P49") (pintype "bidirectional"))
    )
    (net (code "50") (name "Net-(U1-~{SAFEBOOT})") (class "Default")
      (node (ref "R16") (pin "1") (pinfunction "1_1") (pintype "passive"))
      (node (ref "U1") (pin "P50") (pinfunction "~{SAFEBOOT}_P50") (pintype "input"))
    )
    (net (code "51") (name "PPS") (class "Default")
      (node (ref "D2") (pin "A") (pinfunction "A_A") (pintype "passive"))
      (node (ref "J6") (pin "1") (pinfunction "1_1") (pintype "passive"))
      (node (ref "R15") (pin "2") (pinfunction "2_2") (pintype "passive"))
    )
    (net (code "52") (name "RF_IN") (class "Default")
      (node (ref "FB1") (pin "P1") (pinfunction "1_P1") (pintype "passive"))
      (node (ref "J1") (pin "FEED") (pinfunction "SIGNAL_FEED") (pintype "bidirectional"))
      (node (ref "U1") (pin "P2") (pinfunction "RF_IN_P2") (pintype "input"))
    )
    (net (code "53") (name "RTK_STAT") (class "Default")
      (node (ref "D3") (pin "A") (pinfunction "A_A") (pintype "passive"))
      (node (ref "R14") (pin "2") (pinfunction "2_2") (pintype "passive"))
    )
    (net (code "54") (name "RXI2") (class "Default")
      (node (ref "J7") (pin "4") (pinfunction "4_4") (pintype "passive"))
      (node (ref "R12") (pin "2") (pinfunction "2_2") (pintype "passive"))
    )
    (net (code "55") (name "RXI{slash}MOSI") (class "Default")
      (node (ref "J5") (pin "5") (pinfunction "5_5") (pintype "passive"))
      (node (ref "R10") (pin "2") (pinfunction "2_2") (pintype "passive"))
    )
    (net (code "56") (name "SCL{slash}CLK") (class "Default")
      (node (ref "J3") (pin "4") (pinfunction "4_4") (pintype "passive"))
      (node (ref "J4") (pin "4") (pinfunction "4_4") (pintype "passive"))
      (node (ref "J5") (pin "7") (pinfunction "7_7") (pintype "passive"))
      (node (ref "J6") (pin "6") (pinfunction "6_6") (pintype "passive"))
      (node (ref "R19") (pin "1") (pinfunction "1_1") (pintype "passive"))
      (node (ref "R7") (pin "2") (pinfunction "2_2") (pintype "passive"))
    )
    (net (code "57") (name "SHIELD") (class "Default")
      (node (ref "J2") (pin "SHLD1") (pinfunction "SHLD_SHLD1") (pintype "bidirectional"))
      (node (ref "J2") (pin "SHLD2") (pinfunction "SHLD_SHLD2") (pintype "bidirectional"))
      (node (ref "J2") (pin "SHLD3") (pinfunction "SHLD_SHLD3") (pintype "bidirectional"))
      (node (ref "J2") (pin "SHLD4") (pinfunction "SHLD_SHLD4") (pintype "bidirectional"))
    )
    (net (code "58") (name "TXO2") (class "Default")
      (node (ref "J7") (pin "5") (pinfunction "5_5") (pintype "passive"))
      (node (ref "R11") (pin "2") (pinfunction "2_2") (pintype "passive"))
    )
    (net (code "59") (name "TXO{slash}MISO") (class "Default")
      (node (ref "J5") (pin "6") (pinfunction "6_6") (pintype "passive"))
      (node (ref "R9") (pin "2") (pinfunction "2_2") (pintype "passive"))
    )
    (net (code "60") (name "TX_READY") (class "Default")
      (node (ref "J6") (pin "5") (pinfunction "5_5") (pintype "passive"))
      (node (ref "R8") (pin "2") (pinfunction "2_2") (pintype "passive"))
    )
    (net (code "61") (name "VIN") (class "Default")
      (node (ref "C3") (pin "1") (pinfunction "1_1") (pintype "passive"))
      (node (ref "D5") (pin "5") (pinfunction "5_5") (pintype "bidirectional"))
      (node (ref "J2") (pin "VBUS1") (pinfunction "VBUS_VBUS1") (pintype "bidirectional"))
      (node (ref "J2") (pin "VBUS2") (pinfunction "VBUS_VBUS2") (pintype "bidirectional"))
      (node (ref "J5") (pin "2") (pinfunction "2_2") (pintype "passive"))
      (node (ref "U2") (pin "1") (pinfunction "IN_1") (pintype "input"))
      (node (ref "U2") (pin "3") (pinfunction "EN_3") (pintype "input"))
    )
    (net (code "62") (name "V_BATT") (class "Default")
      (node (ref "BT1") (pin "+") (pinfunction "+_+") (pintype "power_in"))
      (node (ref "R28") (pin "1") (pinfunction "1_1") (pintype "passive"))
      (node (ref "U1") (pin "P36") (pinfunction "V_BKCP_P36") (pintype "power_in"))
    )
    (net (code "63") (name "V_RF") (class "Default")
      (node (ref "R17") (pin "2") (pinfunction "2_2") (pintype "passive"))
      (node (ref "U1") (pin "P7") (pinfunction "V_RF_P7") (pintype "output"))
    )
    (net (code "64") (name "WT+") (class "Default")
      (node (ref "J5") (pin "11") (pinfunction "11_11") (pintype "passive"))
      (node (ref "R35") (pin "1") (pinfunction "1_1") (pintype "passive"))
    )
    (net (code "65") (name "WT-") (class "Default")
      (node (ref "C15") (pin "2") (pinfunction "2_2") (pintype "passive"))
      (node (ref "D9") (pin "P1") (pinfunction "A_P1") (pintype "passive"))
      (node (ref "J5") (pin "10") (pinfunction "10_10") (pintype "passive"))
      (node (ref "U4") (pin "P2") (pinfunction "CATHODE1_P2") (pintype "input"))
    )
    (net (code "66") (name "WT_IN") (class "Default")
      (node (ref "R36") (pin "2") (pinfunction "2_2") (pintype "passive"))
      (node (ref "U4") (pin "P1") (pinfunction "ANODE1_P1") (pintype "input"))
    )
    (net (code "67") (name "WT_OUT") (class "Default")
      (node (ref "R2") (pin "1") (pinfunction "1_1") (pintype "passive"))
      (node (ref "U$62") (pin "P4") (pinfunction "Y_P4") (pintype "bidirectional"))
    )
    (net (code "68") (name "WT_SCHMITT") (class "Default")
      (node (ref "R39") (pin "1") (pinfunction "1_1") (pintype "passive"))
      (node (ref "U$62") (pin "P2") (pinfunction "A_P2") (pintype "bidirectional"))
      (node (ref "U4") (pin "P7") (pinfunction "VOUT1_P7") (pintype "output"))
    )
    (net (code "69") (name "unconnected-(J7-Pad2)") (class "Default")
      (node (ref "J7") (pin "2") (pinfunction "2_2") (pintype "passive"))
    )
    (net (code "70") (name "unconnected-(J7-Pad3)") (class "Default")
      (node (ref "J7") (pin "3") (pinfunction "3_3") (pintype "passive"))
    )
    (net (code "71") (name "unconnected-(J7-Pad6)") (class "Default")
      (node (ref "J7") (pin "6") (pinfunction "6_6") (pintype "passive"))
    )
    (net (code "72") (name "unconnected-(U$62-NC-PadP1)") (class "Default")
      (node (ref "U$62") (pin "P1") (pinfunction "NC_P1") (pintype "no_connect"))
    )
    (net (code "73") (name "unconnected-(U$62-NC-PadP5)") (class "Default")
      (node (ref "U$62") (pin "P5") (pinfunction "NC_P5") (pintype "no_connect"))
    )
    (net (code "74") (name "unconnected-(U$63-NC-PadP1)") (class "Default")
      (node (ref "U$63") (pin "P1") (pinfunction "NC_P1") (pintype "no_connect"))
    )
    (net (code "75") (name "unconnected-(U$63-NC-PadP5)") (class "Default")
      (node (ref "U$63") (pin "P5") (pinfunction "NC_P5") (pintype "no_connect"))
    )
    (net (code "76") (name "unconnected-(U1-ANT_DETECT-PadP4)") (class "Default")
      (node (ref "U1") (pin "P4") (pinfunction "ANT_DETECT_P4") (pintype "input"))
    )
    (net (code "77") (name "unconnected-(U1-ANT_OFF-PadP5)") (class "Default")
      (node (ref "U1") (pin "P5") (pinfunction "ANT_OFF_P5") (pintype "output"))
    )
    (net (code "78") (name "unconnected-(U1-RSVD-PadP8)") (class "Default")
      (node (ref "U1") (pin "P8") (pinfunction "RSVD_P8") (pintype "no_connect"))
    )
    (net (code "79") (name "unconnected-(U1-RSVD-PadP9)") (class "Default")
      (node (ref "U1") (pin "P9") (pinfunction "RSVD_P9") (pintype "no_connect"))
    )
    (net (code "80") (name "unconnected-(U1-RSVD-PadP10)") (class "Default")
      (node (ref "U1") (pin "P10") (pinfunction "RSVD_P10") (pintype "no_connect"))
    )
    (net (code "81") (name "unconnected-(U1-RSVD-PadP11)") (class "Default")
      (node (ref "U1") (pin "P11") (pinfunction "RSVD_P11") (pintype "no_connect"))
    )
    (net (code "82") (name "unconnected-(U1-RSVD-PadP13)") (class "Default")
      (node (ref "U1") (pin "P13") (pinfunction "RSVD_P13") (pintype "no_connect"))
    )
    (net (code "83") (name "unconnected-(U1-RSVD-PadP15)") (class "Default")
      (node (ref "U1") (pin "P15") (pinfunction "RSVD_P15") (pintype "no_connect"))
    )
    (net (code "84") (name "unconnected-(U1-RSVD-PadP16)") (class "Default")
      (node (ref "U1") (pin "P16") (pinfunction "RSVD_P16") (pintype "no_connect"))
    )
    (net (code "85") (name "unconnected-(U1-RSVD-PadP17)") (class "Default")
      (node (ref "U1") (pin "P17") (pinfunction "RSVD_P17") (pintype "no_connect"))
    )
    (net (code "86") (name "unconnected-(U1-RSVD-PadP18)") (class "Default")
      (node (ref "U1") (pin "P18") (pinfunction "RSVD_P18") (pintype "no_connect"))
    )
    (net (code "87") (name "unconnected-(U1-RSVD-PadP21)") (class "Default")
      (node (ref "U1") (pin "P21") (pinfunction "RSVD_P21") (pintype "no_connect"))
    )
    (net (code "88") (name "unconnected-(U1-RSVD-PadP24)") (class "Default")
      (node (ref "U1") (pin "P24") (pinfunction "RSVD_P24") (pintype "no_connect"))
    )
    (net (code "89") (name "unconnected-(U1-RSVD-PadP25)") (class "Default")
      (node (ref "U1") (pin "P25") (pinfunction "RSVD_P25") (pintype "no_connect"))
    )
    (net (code "90") (name "unconnected-(U1-RSVD-PadP28)") (class "Default")
      (node (ref "U1") (pin "P28") (pinfunction "RSVD_P28") (pintype "no_connect"))
    )
    (net (code "91") (name "unconnected-(U1-RSVD-PadP29)") (class "Default")
      (node (ref "U1") (pin "P29") (pinfunction "RSVD_P29") (pintype "no_connect"))
    )
    (net (code "92") (name "unconnected-(U1-RSVD-PadP30)") (class "Default")
      (node (ref "U1") (pin "P30") (pinfunction "RSVD_P30") (pintype "no_connect"))
    )
    (net (code "93") (name "unconnected-(U1-RSVD-PadP31)") (class "Default")
      (node (ref "U1") (pin "P31") (pinfunction "RSVD_P31") (pintype "no_connect"))
    )
    (net (code "94") (name "unconnected-(U1-RSVD-PadP35)") (class "Default")
      (node (ref "U1") (pin "P35") (pinfunction "RSVD_P35") (pintype "no_connect"))
    )
    (net (code "95") (name "unconnected-(U1-RSVD-PadP52)") (class "Default")
      (node (ref "U1") (pin "P52") (pinfunction "RSVD_P52") (pintype "no_connect"))
    )
    (net (code "96") (name "unconnected-(U1-RSVD-PadP54)") (class "Default")
      (node (ref "U1") (pin "P54") (pinfunction "RSVD_P54") (pintype "no_connect"))
    )
    (net (code "97") (name "unconnected-(U1-~{ANT_SHORT}-PadP6)") (class "Default")
      (node (ref "U1") (pin "P6") (pinfunction "~{ANT_SHORT}_P6") (pintype "output"))
    )
    (net (code "98") (name "unconnected-(U2-NC-Pad4)") (class "Default")
      (node (ref "U2") (pin "4") (pinfunction "NC_4") (pintype "no_connect"))
    )
  )
)
